# EEPROM_RTC.net
KiCad netlist of a schematic drawn in Altium Designer
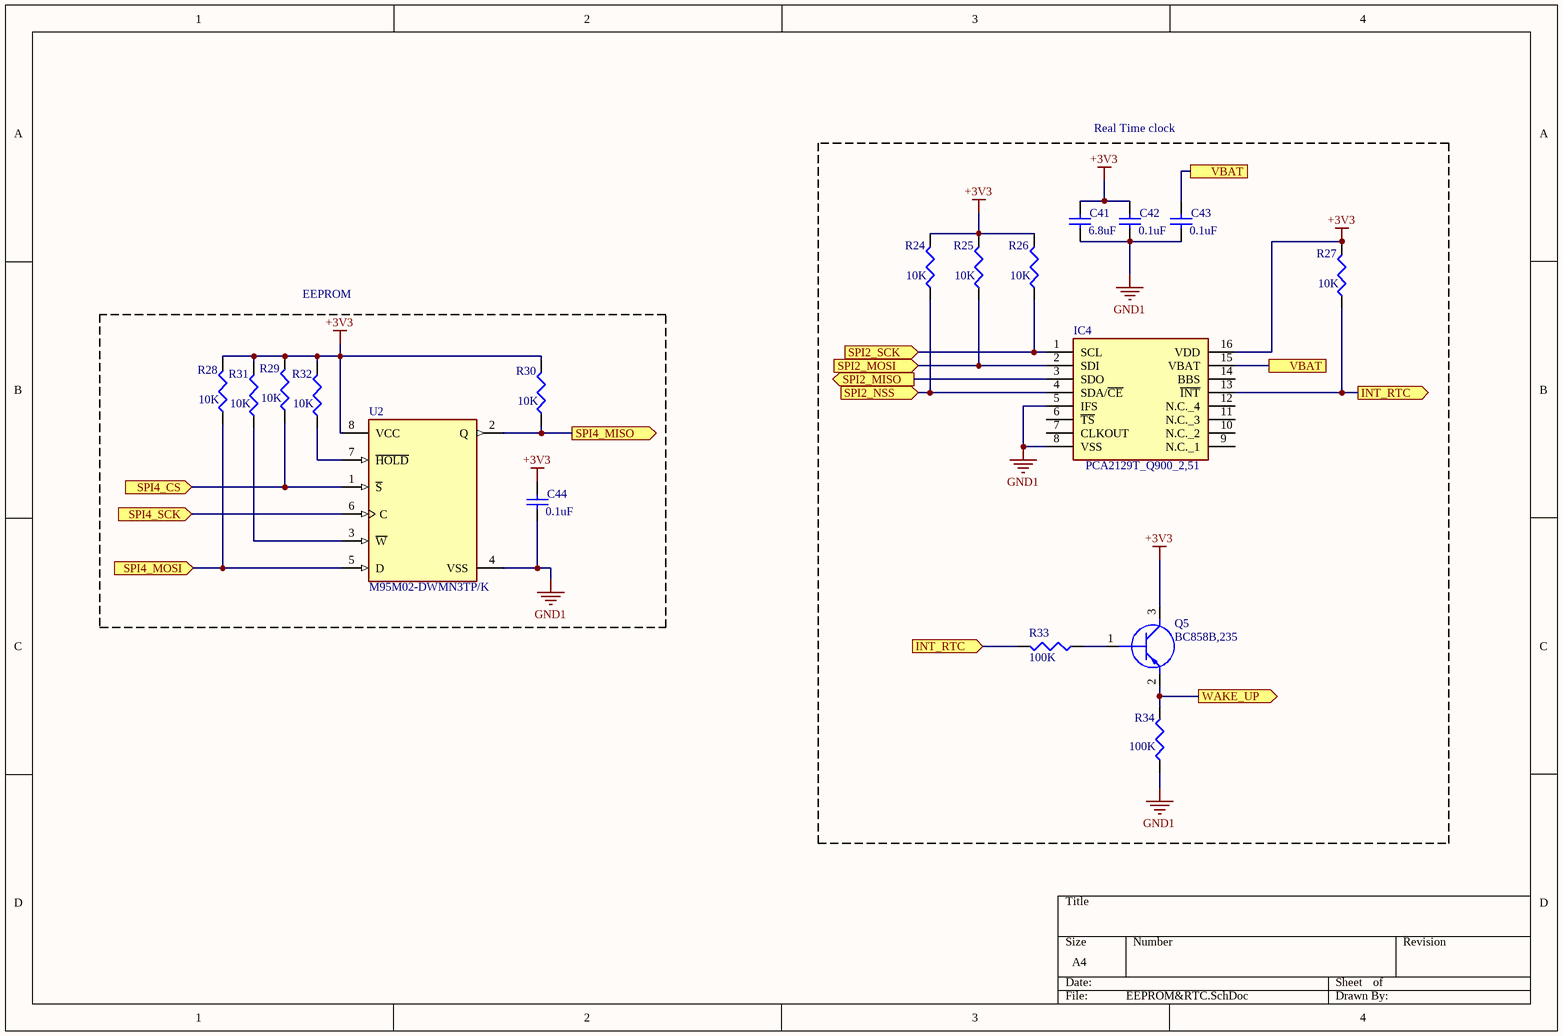
[diagram p0: EEPROM&RTC.SchDoc]

(export (version "E")
  (design (tool "Eeschema 10.0.6"))
  (components
    (comp (ref "C41")
      (value "6.8uF")
      (footprint "1608[0603]")
      (description "Capacitor (Semiconductor SIM Model)")
      (fields (field (name "Comment") "Cap Semi") (field (name "PUBLISHER") "Altium Limited"))
      (libsource (lib "Miscellaneous Devices") (part "Cap Semi"))
    )
    (comp (ref "C42")
      (value "0.1uF")
      (footprint "1608[0603]")
      (description "Capacitor (Semiconductor SIM Model)")
      (fields (field (name "Comment") "Cap Semi") (field (name "PUBLISHER") "Altium Limited"))
      (libsource (lib "Miscellaneous Devices") (part "Cap Semi"))
    )
    (comp (ref "C43")
      (value "0.1uF")
      (footprint "1608[0603]")
      (description "Capacitor (Semiconductor SIM Model)")
      (fields (field (name "Comment") "Cap Semi") (field (name "PUBLISHER") "Altium Limited"))
      (libsource (lib "Miscellaneous Devices") (part "Cap Semi"))
    )
    (comp (ref "C44")
      (value "0.1uF")
      (footprint "1608[0603]")
      (description "Capacitor (Semiconductor SIM Model)")
      (fields (field (name "Comment") "Cap Semi") (field (name "PUBLISHER") "Altium Limited"))
      (libsource (lib "Miscellaneous Devices") (part "Cap Semi"))
    )
    (comp (ref "IC4")
      (value "PCA2129T_Q900_2,51")
      (footprint "SamacSys:SOIC127P1032X265-16N")
      (description "Integrated Circuit")
      (fields
        (field (name "MANUFACTURER_PART_NUMBER") "PCA2129T/Q900/2,51")
        (field (name "MOUSER PART NUMBER") "771-PCA2129TQ900251")
      )
      (libsource (lib "SamacSys") (part "PCA2129T_Q900_2,51"))
    )
    (comp (ref "Q5")
      (value "BC858B,235")
      (footprint "SamacSys:SOT95P230X110-3N")
      (description "Transistor BJT PNP")
      (fields (field (name "MOUSER PART NUMBER") "771-BC858B235"))
      (libsource (lib "SamacSys") (part "BC858B,235"))
    )
    (comp (ref "R24")
      (value "10K")
      (footprint "J1-0603")
      (description "Resistor")
      (fields (field (name "Comment") "Res3") (field (name "PUBLISHER") "Altium Limited"))
      (libsource (lib "Miscellaneous Devices") (part "Res3"))
    )
    (comp (ref "R25")
      (value "10K")
      (footprint "J1-0603")
      (description "Resistor")
      (fields (field (name "Comment") "Res3") (field (name "PUBLISHER") "Altium Limited"))
      (libsource (lib "Miscellaneous Devices") (part "Res3"))
    )
    (comp (ref "R26")
      (value "10K")
      (footprint "J1-0603")
      (description "Resistor")
      (fields (field (name "Comment") "Res3") (field (name "PUBLISHER") "Altium Limited"))
      (libsource (lib "Miscellaneous Devices") (part "Res3"))
    )
    (comp (ref "R27")
      (value "10K")
      (footprint "J1-0603")
      (description "Resistor")
      (fields (field (name "Comment") "Res3") (field (name "PUBLISHER") "Altium Limited"))
      (libsource (lib "Miscellaneous Devices") (part "Res3"))
    )
    (comp (ref "R28")
      (value "10K")
      (footprint "J1-0603")
      (description "Resistor")
      (fields (field (name "Comment") "Res3") (field (name "PUBLISHER") "Altium Limited"))
      (libsource (lib "Miscellaneous Devices") (part "Res3"))
    )
    (comp (ref "R29")
      (value "10K")
      (footprint "J1-0603")
      (description "Resistor")
      (fields (field (name "Comment") "Res3") (field (name "PUBLISHER") "Altium Limited"))
      (libsource (lib "Miscellaneous Devices") (part "Res3"))
    )
    (comp (ref "R30")
      (value "10K")
      (footprint "J1-0603")
      (description "Resistor")
      (fields (field (name "Comment") "Res3") (field (name "PUBLISHER") "Altium Limited"))
      (libsource (lib "Miscellaneous Devices") (part "Res3"))
    )
    (comp (ref "R31")
      (value "10K")
      (footprint "J1-0603")
      (description "Resistor")
      (fields (field (name "Comment") "Res3") (field (name "PUBLISHER") "Altium Limited"))
      (libsource (lib "Miscellaneous Devices") (part "Res3"))
    )
    (comp (ref "R32")
      (value "10K")
      (footprint "J1-0603")
      (description "Resistor")
      (fields (field (name "Comment") "Res3") (field (name "PUBLISHER") "Altium Limited"))
      (libsource (lib "Miscellaneous Devices") (part "Res3"))
    )
    (comp (ref "R33")
      (value "100K")
      (footprint "J1-0603")
      (description "Resistor")
      (fields (field (name "Comment") "Res3") (field (name "PUBLISHER") "Altium Limited"))
      (libsource (lib "Miscellaneous Devices") (part "Res3"))
    )
    (comp (ref "R34")
      (value "100K")
      (footprint "J1-0603")
      (description "Resistor")
      (fields (field (name "Comment") "Res3") (field (name "PUBLISHER") "Altium Limited"))
      (libsource (lib "Miscellaneous Devices") (part "Res3"))
    )
    (comp (ref "U2")
      (value "M95M02-DWMN3TP/K")
      (footprint "FP-SO8N-SO-A-MFG")
      (description "IC EEPROM 2M SPI 10MHZ 8SO")
      (fields
        (field (name "OCTOPART") "https://octopart.com/m95m02-dwmn3tp%2Fk-stmicroelectronics-52112703")
        (field (name "MANUFACTURER") "STMicroelectronics")
      )
      (libsource (lib "Altium Content Vault") (part "a83b3ca3e2b52f5da19b03283f87d3c"))
    )
  )
  (nets
    (net (code "1") (name "+3V3") (class "Default")
      (node (ref "C41") (pin "2") (pinfunction "2_2") (pintype "passive"))
      (node (ref "C42") (pin "2") (pinfunction "2_2") (pintype "passive"))
      (node (ref "C44") (pin "2") (pinfunction "2_2") (pintype "passive"))
      (node (ref "IC4") (pin "16") (pinfunction "VDD_16") (pintype "passive"))
      (node (ref "Q5") (pin "3") (pinfunction "C_3") (pintype "passive"))
      (node (ref "R24") (pin "2") (pinfunction "2_2") (pintype "passive"))
      (node (ref "R25") (pin "2") (pinfunction "2_2") (pintype "passive"))
      (node (ref "R26") (pin "2") (pinfunction "2_2") (pintype "passive"))
      (node (ref "R27") (pin "2") (pinfunction "2_2") (pintype "passive"))
      (node (ref "R28") (pin "2") (pinfunction "2_2") (pintype "passive"))
      (node (ref "R29") (pin "2") (pinfunction "2_2") (pintype "passive"))
      (node (ref "R30") (pin "2") (pinfunction "2_2") (pintype "passive"))
      (node (ref "R31") (pin "2") (pinfunction "2_2") (pintype "passive"))
      (node (ref "R32") (pin "2") (pinfunction "2_2") (pintype "passive"))
      (node (ref "U2") (pin "8") (pinfunction "VCC_8") (pintype "power_in"))
    )
    (net (code "2") (name "/INT_RTC") (class "Default")
      (node (ref "IC4") (pin "13") (pinfunction "~{INT}_13") (pintype "passive"))
      (node (ref "R27") (pin "1") (pinfunction "1_1") (pintype "passive"))
      (node (ref "R33") (pin "2") (pinfunction "2_2") (pintype "passive"))
    )
    (net (code "3") (name "/SPI2_MISO") (class "Default")
      (node (ref "IC4") (pin "3") (pinfunction "SDO_3") (pintype "passive"))
    )
    (net (code "4") (name "/SPI2_MOSI") (class "Default")
      (node (ref "IC4") (pin "2") (pinfunction "SDI_2") (pintype "passive"))
      (node (ref "R25") (pin "1") (pinfunction "1_1") (pintype "passive"))
    )
    (net (code "5") (name "/SPI2_NSS") (class "Default")
      (node (ref "IC4") (pin "4") (pinfunction "SDA/~{CE}_4") (pintype "passive"))
      (node (ref "R24") (pin "1") (pinfunction "1_1") (pintype "passive"))
    )
    (net (code "6") (name "/SPI2_SCK") (class "Default")
      (node (ref "IC4") (pin "1") (pinfunction "SCL_1") (pintype "passive"))
      (node (ref "R26") (pin "1") (pinfunction "1_1") (pintype "passive"))
    )
    (net (code "7") (name "/SPI4_CS") (class "Default")
      (node (ref "R29") (pin "1") (pinfunction "1_1") (pintype "passive"))
      (node (ref "U2") (pin "1") (pinfunction "~{S}_1") (pintype "input"))
    )
    (net (code "8") (name "/SPI4_MISO") (class "Default")
      (node (ref "R30") (pin "1") (pinfunction "1_1") (pintype "passive"))
      (node (ref "U2") (pin "2") (pinfunction "Q_2") (pintype "output"))
    )
    (net (code "9") (name "/SPI4_MOSI") (class "Default")
      (node (ref "R28") (pin "1") (pinfunction "1_1") (pintype "passive"))
      (node (ref "U2") (pin "5") (pinfunction "D_5") (pintype "input"))
    )
    (net (code "10") (name "/SPI4_SCK") (class "Default")
      (node (ref "U2") (pin "6") (pinfunction "C_6") (pintype "input"))
    )
    (net (code "11") (name "/VBAT") (class "Default")
      (node (ref "C43") (pin "2") (pinfunction "2_2") (pintype "passive"))
      (node (ref "IC4") (pin "15") (pinfunction "VBAT_15") (pintype "passive"))
    )
    (net (code "12") (name "/WAKE_UP") (class "Default")
      (node (ref "Q5") (pin "2") (pinfunction "E_2") (pintype "passive"))
      (node (ref "R34") (pin "2") (pinfunction "2_2") (pintype "passive"))
    )
    (net (code "13") (name "GND1") (class "Default")
      (node (ref "C41") (pin "1") (pinfunction "1_1") (pintype "passive"))
      (node (ref "C42") (pin "1") (pinfunction "1_1") (pintype "passive"))
      (node (ref "C43") (pin "1") (pinfunction "1_1") (pintype "passive"))
      (node (ref "C44") (pin "1") (pinfunction "1_1") (pintype "passive"))
      (node (ref "IC4") (pin "5") (pinfunction "IFS_5") (pintype "passive"))
      (node (ref "IC4") (pin "8") (pinfunction "VSS_8") (pintype "passive"))
      (node (ref "R34") (pin "1") (pinfunction "1_1") (pintype "passive"))
      (node (ref "U2") (pin "4") (pinfunction "VSS_4") (pintype "power_in"))
    )
    (net (code "14") (name "Net-(Q5-B)") (class "Default")
      (node (ref "Q5") (pin "1") (pinfunction "B_1") (pintype "passive"))
      (node (ref "R33") (pin "1") (pinfunction "1_1") (pintype "passive"))
    )
    (net (code "15") (name "Net-(U2-~{HOLD})") (class "Default")
      (node (ref "R32") (pin "1") (pinfunction "1_1") (pintype "passive"))
      (node (ref "U2") (pin "7") (pinfunction "~{HOLD}_7") (pintype "input"))
    )
    (net (code "16") (name "Net-(U2-~{W})") (class "Default")
      (node (ref "R31") (pin "1") (pinfunction "1_1") (pintype "passive"))
      (node (ref "U2") (pin "3") (pinfunction "~{W}_3") (pintype "input"))
    )
    (net (code "17") (name "unconnected-(IC4-BBS-Pad14)") (class "Default")
      (node (ref "IC4") (pin "14") (pinfunction "BBS_14") (pintype "passive"))
    )
    (net (code "18") (name "unconnected-(IC4-CLKOUT-Pad7)") (class "Default")
      (node (ref "IC4") (pin "7") (pinfunction "CLKOUT_7") (pintype "passive"))
    )
    (net (code "19") (name "unconnected-(IC4-N.C._1-Pad9)") (class "Default")
      (node (ref "IC4") (pin "9") (pinfunction "N.C._1_9") (pintype "passive"))
    )
    (net (code "20") (name "unconnected-(IC4-N.C._2-Pad10)") (class "Default")
      (node (ref "IC4") (pin "10") (pinfunction "N.C._2_10") (pintype "passive"))
    )
    (net (code "21") (name "unconnected-(IC4-N.C._3-Pad11)") (class "Default")
      (node (ref "IC4") (pin "11") (pinfunction "N.C._3_11") (pintype "passive"))
    )
    (net (code "22") (name "unconnected-(IC4-N.C._4-Pad12)") (class "Default")
      (node (ref "IC4") (pin "12") (pinfunction "N.C._4_12") (pintype "passive"))
    )
    (net (code "23") (name "unconnected-(IC4-~{TS}-Pad6)") (class "Default")
      (node (ref "IC4") (pin "6") (pinfunction "~{TS}_6") (pintype "passive"))
    )
  )
)
